# mrShark_LED-Marker.net
KiCad netlist of a schematic drawn in EAGLE
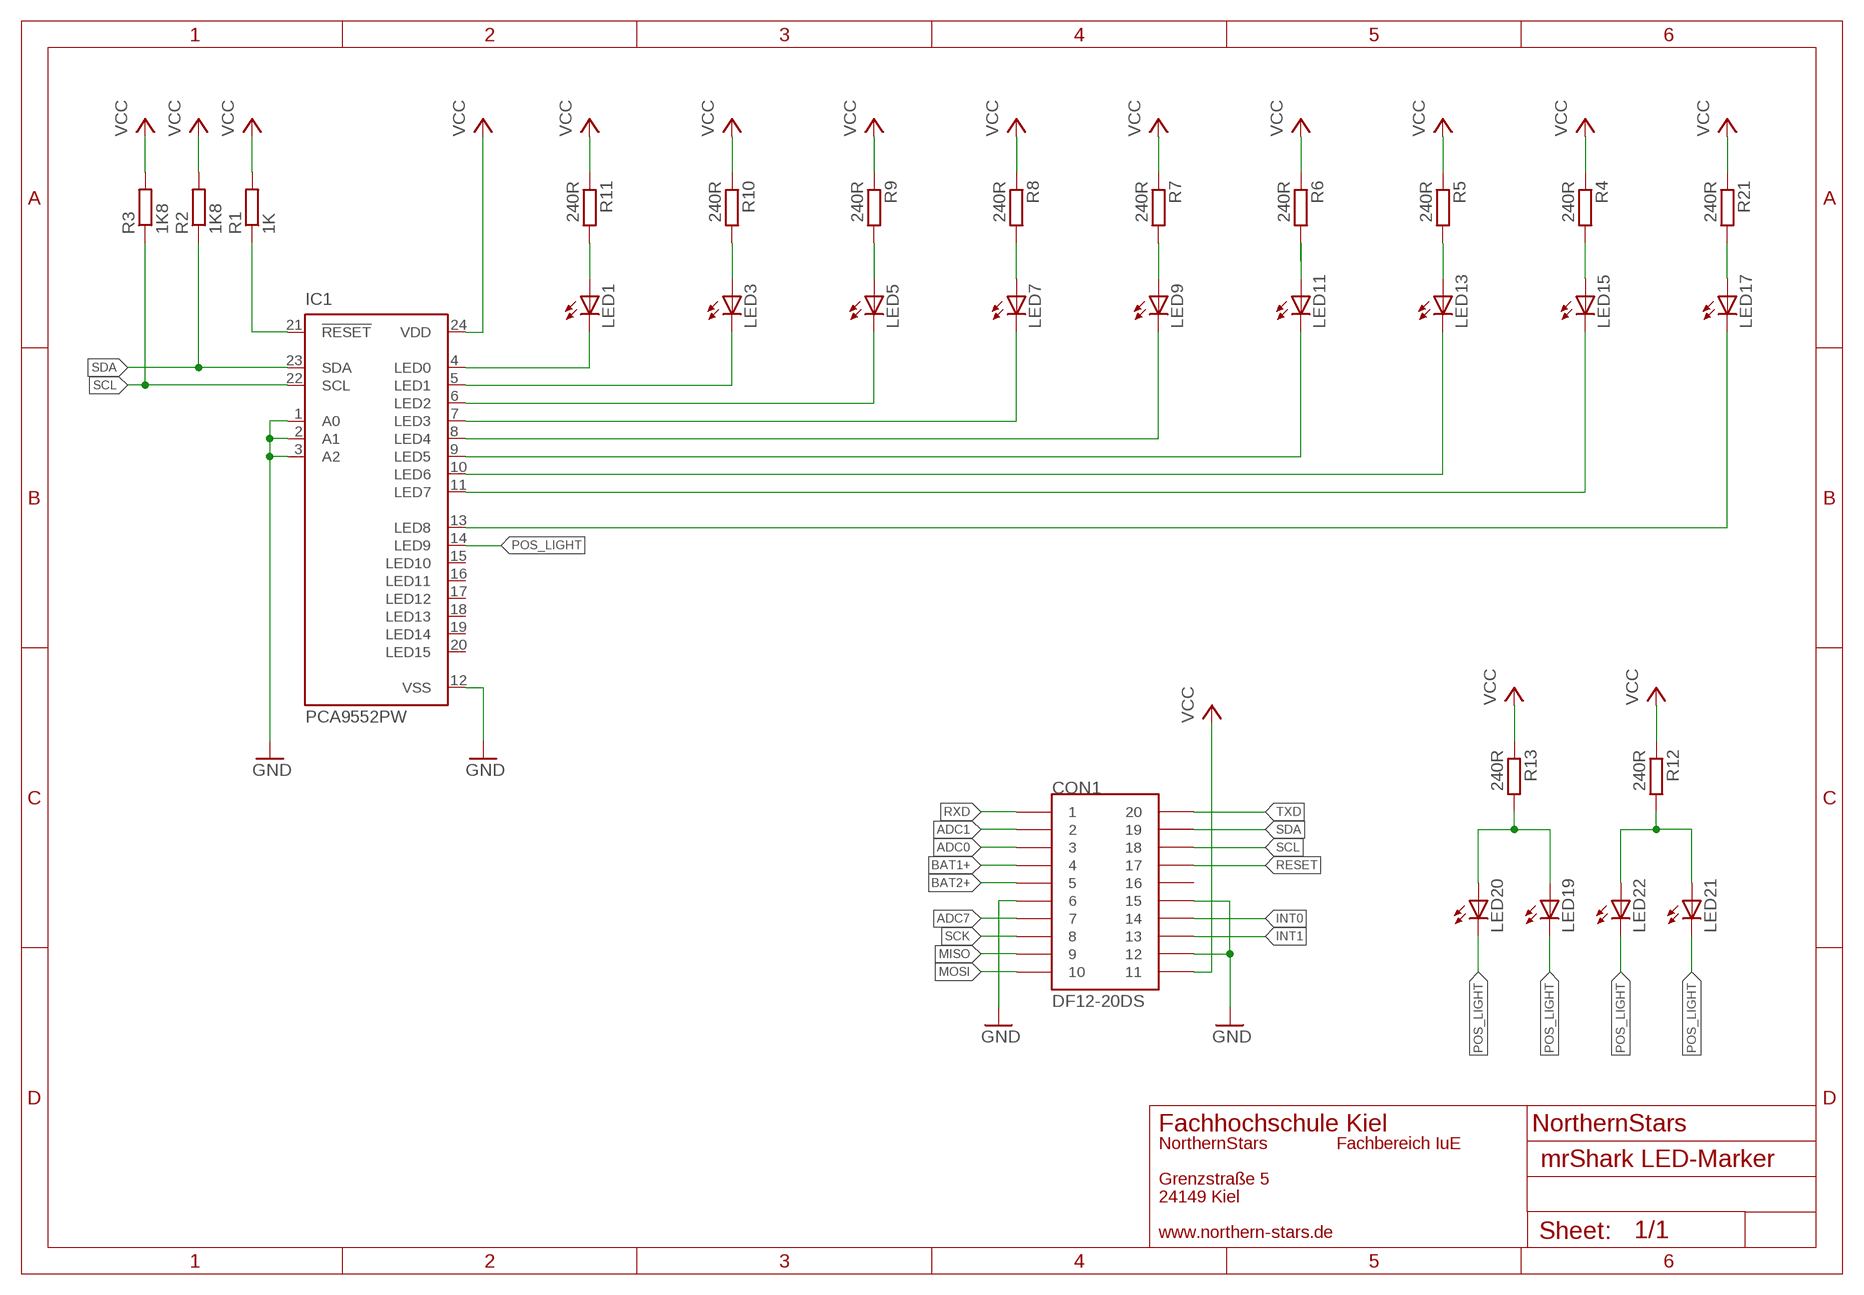
[diagram p0: schematic, sheet 1]

(export (version "E")
  (design (tool "Eeschema 10.0.6"))
  (components
    (comp (ref "CON1")
      (value "DF12-20DS")
      (footprint "eagle-import:DF12-20DS")
      (libsource (lib "eagle-import") (part "DF12-20DS"))
    )
    (comp (ref "IC1")
      (value "PCA9552PW")
      (footprint "eagle-import:TSSOP24")
      (libsource (lib "eagle-import") (part "PCA9552PW"))
    )
    (comp (ref "LED1")
      (value "LEDCHIPLED_0603")
      (footprint "eagle-import:CHIPLED_0603")
      (libsource (lib "eagle-import") (part "LEDCHIPLED_0603"))
    )
    (comp (ref "LED3")
      (value "LEDCHIPLED_0603")
      (footprint "eagle-import:CHIPLED_0603")
      (libsource (lib "eagle-import") (part "LEDCHIPLED_0603"))
    )
    (comp (ref "LED5")
      (value "LEDCHIPLED_0603")
      (footprint "eagle-import:CHIPLED_0603")
      (libsource (lib "eagle-import") (part "LEDCHIPLED_0603"))
    )
    (comp (ref "LED7")
      (value "LEDCHIPLED_0603")
      (footprint "eagle-import:CHIPLED_0603")
      (libsource (lib "eagle-import") (part "LEDCHIPLED_0603"))
    )
    (comp (ref "LED9")
      (value "LEDCHIPLED_0603")
      (footprint "eagle-import:CHIPLED_0603")
      (libsource (lib "eagle-import") (part "LEDCHIPLED_0603"))
    )
    (comp (ref "LED11")
      (value "LEDCHIPLED_0603")
      (footprint "eagle-import:CHIPLED_0603")
      (libsource (lib "eagle-import") (part "LEDCHIPLED_0603"))
    )
    (comp (ref "LED13")
      (value "LEDCHIPLED_0603")
      (footprint "eagle-import:CHIPLED_0603")
      (libsource (lib "eagle-import") (part "LEDCHIPLED_0603"))
    )
    (comp (ref "LED15")
      (value "LEDCHIPLED_0603")
      (footprint "eagle-import:CHIPLED_0603")
      (libsource (lib "eagle-import") (part "LEDCHIPLED_0603"))
    )
    (comp (ref "LED17")
      (value "LEDCHIPLED_0603")
      (footprint "eagle-import:CHIPLED_0603")
      (libsource (lib "eagle-import") (part "LEDCHIPLED_0603"))
    )
    (comp (ref "LED19")
      (value "LEDCHIPLED_0603")
      (footprint "eagle-import:CHIPLED_0603")
      (libsource (lib "eagle-import") (part "LEDCHIPLED_0603"))
    )
    (comp (ref "LED20")
      (value "LEDCHIPLED_0603")
      (footprint "eagle-import:CHIPLED_0603")
      (libsource (lib "eagle-import") (part "LEDCHIPLED_0603"))
    )
    (comp (ref "LED21")
      (value "LEDCHIPLED_0603")
      (footprint "eagle-import:CHIPLED_0603")
      (libsource (lib "eagle-import") (part "LEDCHIPLED_0603"))
    )
    (comp (ref "LED22")
      (value "LEDCHIPLED_0603")
      (footprint "eagle-import:CHIPLED_0603")
      (libsource (lib "eagle-import") (part "LEDCHIPLED_0603"))
    )
    (comp (ref "R1")
      (value "1K")
      (footprint "eagle-import:R0603")
      (libsource (lib "eagle-import") (part "R-EU_R0603"))
    )
    (comp (ref "R2")
      (value "1K8")
      (footprint "eagle-import:R0603")
      (libsource (lib "eagle-import") (part "R-EU_R0603"))
    )
    (comp (ref "R3")
      (value "1K8")
      (footprint "eagle-import:R0603")
      (libsource (lib "eagle-import") (part "R-EU_R0603"))
    )
    (comp (ref "R4")
      (value "240R")
      (footprint "eagle-import:R0603")
      (libsource (lib "eagle-import") (part "R-EU_R0603"))
    )
    (comp (ref "R5")
      (value "240R")
      (footprint "eagle-import:R0603")
      (libsource (lib "eagle-import") (part "R-EU_R0603"))
    )
    (comp (ref "R6")
      (value "240R")
      (footprint "eagle-import:R0603")
      (libsource (lib "eagle-import") (part "R-EU_R0603"))
    )
    (comp (ref "R7")
      (value "240R")
      (footprint "eagle-import:R0603")
      (libsource (lib "eagle-import") (part "R-EU_R0603"))
    )
    (comp (ref "R8")
      (value "240R")
      (footprint "eagle-import:R0603")
      (libsource (lib "eagle-import") (part "R-EU_R0603"))
    )
    (comp (ref "R9")
      (value "240R")
      (footprint "eagle-import:R0603")
      (libsource (lib "eagle-import") (part "R-EU_R0603"))
    )
    (comp (ref "R10")
      (value "240R")
      (footprint "eagle-import:R0603")
      (libsource (lib "eagle-import") (part "R-EU_R0603"))
    )
    (comp (ref "R11")
      (value "240R")
      (footprint "eagle-import:R0603")
      (libsource (lib "eagle-import") (part "R-EU_R0603"))
    )
    (comp (ref "R12")
      (value "240R")
      (footprint "eagle-import:R0603")
      (libsource (lib "eagle-import") (part "R-EU_R0603"))
    )
    (comp (ref "R13")
      (value "240R")
      (footprint "eagle-import:R0603")
      (libsource (lib "eagle-import") (part "R-EU_R0603"))
    )
    (comp (ref "R21")
      (value "240R")
      (footprint "eagle-import:R0603")
      (libsource (lib "eagle-import") (part "R-EU_R0603"))
    )
  )
  (nets
    (net (code "1") (name "ADC0") (class "Default")
      (node (ref "CON1") (pin "3") (pinfunction "3_3") (pintype "bidirectional"))
    )
    (net (code "2") (name "ADC1") (class "Default")
      (node (ref "CON1") (pin "2") (pinfunction "2_2") (pintype "bidirectional"))
    )
    (net (code "3") (name "ADC7") (class "Default")
      (node (ref "CON1") (pin "7") (pinfunction "7_7") (pintype "bidirectional"))
    )
    (net (code "4") (name "BAT1+") (class "Default")
      (node (ref "CON1") (pin "4") (pinfunction "4_4") (pintype "bidirectional"))
    )
    (net (code "5") (name "BAT2+") (class "Default")
      (node (ref "CON1") (pin "5") (pinfunction "5_5") (pintype "bidirectional"))
    )
    (net (code "6") (name "GND") (class "Default")
      (node (ref "CON1") (pin "12") (pinfunction "12_12") (pintype "bidirectional"))
      (node (ref "CON1") (pin "15") (pinfunction "15_15") (pintype "bidirectional"))
      (node (ref "CON1") (pin "6") (pinfunction "6_6") (pintype "bidirectional"))
      (node (ref "IC1") (pin "1") (pinfunction "A0_1") (pintype "input"))
      (node (ref "IC1") (pin "12") (pinfunction "VSS_12") (pintype "power_in"))
      (node (ref "IC1") (pin "2") (pinfunction "A1_2") (pintype "input"))
      (node (ref "IC1") (pin "3") (pinfunction "A2_3") (pintype "input"))
    )
    (net (code "7") (name "INT0") (class "Default")
      (node (ref "CON1") (pin "14") (pinfunction "14_14") (pintype "bidirectional"))
    )
    (net (code "8") (name "INT1") (class "Default")
      (node (ref "CON1") (pin "13") (pinfunction "13_13") (pintype "bidirectional"))
    )
    (net (code "9") (name "MISO") (class "Default")
      (node (ref "CON1") (pin "9") (pinfunction "9_9") (pintype "bidirectional"))
    )
    (net (code "10") (name "MOSI") (class "Default")
      (node (ref "CON1") (pin "10") (pinfunction "10_10") (pintype "bidirectional"))
    )
    (net (code "11") (name "Net-(IC1-LED0)") (class "Default")
      (node (ref "IC1") (pin "4") (pinfunction "LED0_4") (pintype "bidirectional"))
      (node (ref "LED1") (pin "C") (pinfunction "C_C") (pintype "passive"))
    )
    (net (code "12") (name "Net-(IC1-LED1)") (class "Default")
      (node (ref "IC1") (pin "5") (pinfunction "LED1_5") (pintype "bidirectional"))
      (node (ref "LED3") (pin "C") (pinfunction "C_C") (pintype "passive"))
    )
    (net (code "13") (name "Net-(IC1-LED2)") (class "Default")
      (node (ref "IC1") (pin "6") (pinfunction "LED2_6") (pintype "bidirectional"))
      (node (ref "LED5") (pin "C") (pinfunction "C_C") (pintype "passive"))
    )
    (net (code "14") (name "Net-(IC1-LED3)") (class "Default")
      (node (ref "IC1") (pin "7") (pinfunction "LED3_7") (pintype "bidirectional"))
      (node (ref "LED7") (pin "C") (pinfunction "C_C") (pintype "passive"))
    )
    (net (code "15") (name "Net-(IC1-LED4)") (class "Default")
      (node (ref "IC1") (pin "8") (pinfunction "LED4_8") (pintype "bidirectional"))
      (node (ref "LED9") (pin "C") (pinfunction "C_C") (pintype "passive"))
    )
    (net (code "16") (name "Net-(IC1-LED5)") (class "Default")
      (node (ref "IC1") (pin "9") (pinfunction "LED5_9") (pintype "bidirectional"))
      (node (ref "LED11") (pin "C") (pinfunction "C_C") (pintype "passive"))
    )
    (net (code "17") (name "Net-(IC1-LED6)") (class "Default")
      (node (ref "IC1") (pin "10") (pinfunction "LED6_10") (pintype "bidirectional"))
      (node (ref "LED13") (pin "C") (pinfunction "C_C") (pintype "passive"))
    )
    (net (code "18") (name "Net-(IC1-LED7)") (class "Default")
      (node (ref "IC1") (pin "11") (pinfunction "LED7_11") (pintype "bidirectional"))
      (node (ref "LED15") (pin "C") (pinfunction "C_C") (pintype "passive"))
    )
    (net (code "19") (name "Net-(IC1-LED8)") (class "Default")
      (node (ref "IC1") (pin "13") (pinfunction "LED8_13") (pintype "bidirectional"))
      (node (ref "LED17") (pin "C") (pinfunction "C_C") (pintype "passive"))
    )
    (net (code "20") (name "Net-(IC1-~{RESET})") (class "Default")
      (node (ref "IC1") (pin "21") (pinfunction "~{RESET}_21") (pintype "bidirectional"))
      (node (ref "R1") (pin "1") (pinfunction "1_1") (pintype "passive"))
    )
    (net (code "21") (name "Net-(LED1-PadA)") (class "Default")
      (node (ref "LED1") (pin "A") (pinfunction "A_A") (pintype "passive"))
      (node (ref "R11") (pin "2") (pinfunction "2_2") (pintype "passive"))
    )
    (net (code "22") (name "Net-(LED3-PadA)") (class "Default")
      (node (ref "LED3") (pin "A") (pinfunction "A_A") (pintype "passive"))
      (node (ref "R10") (pin "2") (pinfunction "2_2") (pintype "passive"))
    )
    (net (code "23") (name "Net-(LED5-PadA)") (class "Default")
      (node (ref "LED5") (pin "A") (pinfunction "A_A") (pintype "passive"))
      (node (ref "R9") (pin "2") (pinfunction "2_2") (pintype "passive"))
    )
    (net (code "24") (name "Net-(LED7-PadA)") (class "Default")
      (node (ref "LED7") (pin "A") (pinfunction "A_A") (pintype "passive"))
      (node (ref "R8") (pin "2") (pinfunction "2_2") (pintype "passive"))
    )
    (net (code "25") (name "Net-(LED9-PadA)") (class "Default")
      (node (ref "LED9") (pin "A") (pinfunction "A_A") (pintype "passive"))
      (node (ref "R7") (pin "2") (pinfunction "2_2") (pintype "passive"))
    )
    (net (code "26") (name "Net-(LED11-PadA)") (class "Default")
      (node (ref "LED11") (pin "A") (pinfunction "A_A") (pintype "passive"))
      (node (ref "R6") (pin "2") (pinfunction "2_2") (pintype "passive"))
    )
    (net (code "27") (name "Net-(LED13-PadA)") (class "Default")
      (node (ref "LED13") (pin "A") (pinfunction "A_A") (pintype "passive"))
      (node (ref "R5") (pin "2") (pinfunction "2_2") (pintype "passive"))
    )
    (net (code "28") (name "Net-(LED15-PadA)") (class "Default")
      (node (ref "LED15") (pin "A") (pinfunction "A_A") (pintype "passive"))
      (node (ref "R4") (pin "2") (pinfunction "2_2") (pintype "passive"))
    )
    (net (code "29") (name "Net-(LED17-PadA)") (class "Default")
      (node (ref "LED17") (pin "A") (pinfunction "A_A") (pintype "passive"))
      (node (ref "R21") (pin "2") (pinfunction "2_2") (pintype "passive"))
    )
    (net (code "30") (name "Net-(LED19-PadA)") (class "Default")
      (node (ref "LED19") (pin "A") (pinfunction "A_A") (pintype "passive"))
      (node (ref "LED20") (pin "A") (pinfunction "A_A") (pintype "passive"))
      (node (ref "R13") (pin "2") (pinfunction "2_2") (pintype "passive"))
    )
    (net (code "31") (name "Net-(LED21-PadA)") (class "Default")
      (node (ref "LED21") (pin "A") (pinfunction "A_A") (pintype "passive"))
      (node (ref "LED22") (pin "A") (pinfunction "A_A") (pintype "passive"))
      (node (ref "R12") (pin "2") (pinfunction "2_2") (pintype "passive"))
    )
    (net (code "32") (name "POS_LIGHT") (class "Default")
      (node (ref "IC1") (pin "14") (pinfunction "LED9_14") (pintype "bidirectional"))
      (node (ref "LED19") (pin "C") (pinfunction "C_C") (pintype "passive"))
      (node (ref "LED20") (pin "C") (pinfunction "C_C") (pintype "passive"))
      (node (ref "LED21") (pin "C") (pinfunction "C_C") (pintype "passive"))
      (node (ref "LED22") (pin "C") (pinfunction "C_C") (pintype "passive"))
    )
    (net (code "33") (name "RESET") (class "Default")
      (node (ref "CON1") (pin "17") (pinfunction "17_17") (pintype "bidirectional"))
    )
    (net (code "34") (name "RXD") (class "Default")
      (node (ref "CON1") (pin "1") (pinfunction "1_1") (pintype "bidirectional"))
    )
    (net (code "35") (name "SCK") (class "Default")
      (node (ref "CON1") (pin "8") (pinfunction "8_8") (pintype "bidirectional"))
    )
    (net (code "36") (name "SCL") (class "Default")
      (node (ref "CON1") (pin "18") (pinfunction "18_18") (pintype "bidirectional"))
      (node (ref "IC1") (pin "22") (pinfunction "SCL_22") (pintype "input"))
      (node (ref "R3") (pin "1") (pinfunction "1_1") (pintype "passive"))
    )
    (net (code "37") (name "SDA") (class "Default")
      (node (ref "CON1") (pin "19") (pinfunction "19_19") (pintype "bidirectional"))
      (node (ref "IC1") (pin "23") (pinfunction "SDA_23") (pintype "bidirectional"))
      (node (ref "R2") (pin "1") (pinfunction "1_1") (pintype "passive"))
    )
    (net (code "38") (name "TXD") (class "Default")
      (node (ref "CON1") (pin "20") (pinfunction "20_20") (pintype "bidirectional"))
    )
    (net (code "39") (name "VCC") (class "Default")
      (node (ref "CON1") (pin "11") (pinfunction "11_11") (pintype "bidirectional"))
      (node (ref "IC1") (pin "24") (pinfunction "VDD_24") (pintype "power_in"))
      (node (ref "R1") (pin "2") (pinfunction "2_2") (pintype "passive"))
      (node (ref "R10") (pin "1") (pinfunction "1_1") (pintype "passive"))
      (node (ref "R11") (pin "1") (pinfunction "1_1") (pintype "passive"))
      (node (ref "R12") (pin "1") (pinfunction "1_1") (pintype "passive"))
      (node (ref "R13") (pin "1") (pinfunction "1_1") (pintype "passive"))
      (node (ref "R2") (pin "2") (pinfunction "2_2") (pintype "passive"))
      (node (ref "R21") (pin "1") (pinfunction "1_1") (pintype "passive"))
      (node (ref "R3") (pin "2") (pinfunction "2_2") (pintype "passive"))
      (node (ref "R4") (pin "1") (pinfunction "1_1") (pintype "passive"))
      (node (ref "R5") (pin "1") (pinfunction "1_1") (pintype "passive"))
      (node (ref "R6") (pin "1") (pinfunction "1_1") (pintype "passive"))
      (node (ref "R7") (pin "1") (pinfunction "1_1") (pintype "passive"))
      (node (ref "R8") (pin "1") (pinfunction "1_1") (pintype "passive"))
      (node (ref "R9") (pin "1") (pinfunction "1_1") (pintype "passive"))
    )
    (net (code "40") (name "unconnected-(CON1-Pad16)") (class "Default")
      (node (ref "CON1") (pin "16") (pinfunction "16_16") (pintype "bidirectional"))
    )
    (net (code "41") (name "unconnected-(IC1-LED10-Pad15)") (class "Default")
      (node (ref "IC1") (pin "15") (pinfunction "LED10_15") (pintype "bidirectional"))
    )
    (net (code "42") (name "unconnected-(IC1-LED11-Pad16)") (class "Default")
      (node (ref "IC1") (pin "16") (pinfunction "LED11_16") (pintype "bidirectional"))
    )
    (net (code "43") (name "unconnected-(IC1-LED12-Pad17)") (class "Default")
      (node (ref "IC1") (pin "17") (pinfunction "LED12_17") (pintype "bidirectional"))
    )
    (net (code "44") (name "unconnected-(IC1-LED13-Pad18)") (class "Default")
      (node (ref "IC1") (pin "18") (pinfunction "LED13_18") (pintype "bidirectional"))
    )
    (net (code "45") (name "unconnected-(IC1-LED14-Pad19)") (class "Default")
      (node (ref "IC1") (pin "19") (pinfunction "LED14_19") (pintype "bidirectional"))
    )
    (net (code "46") (name "unconnected-(IC1-LED15-Pad20)") (class "Default")
      (node (ref "IC1") (pin "20") (pinfunction "LED15_20") (pintype "bidirectional"))
    )
  )
)
